# iso_sincs.net
KiCad netlist of a schematic drawn in Altium Designer
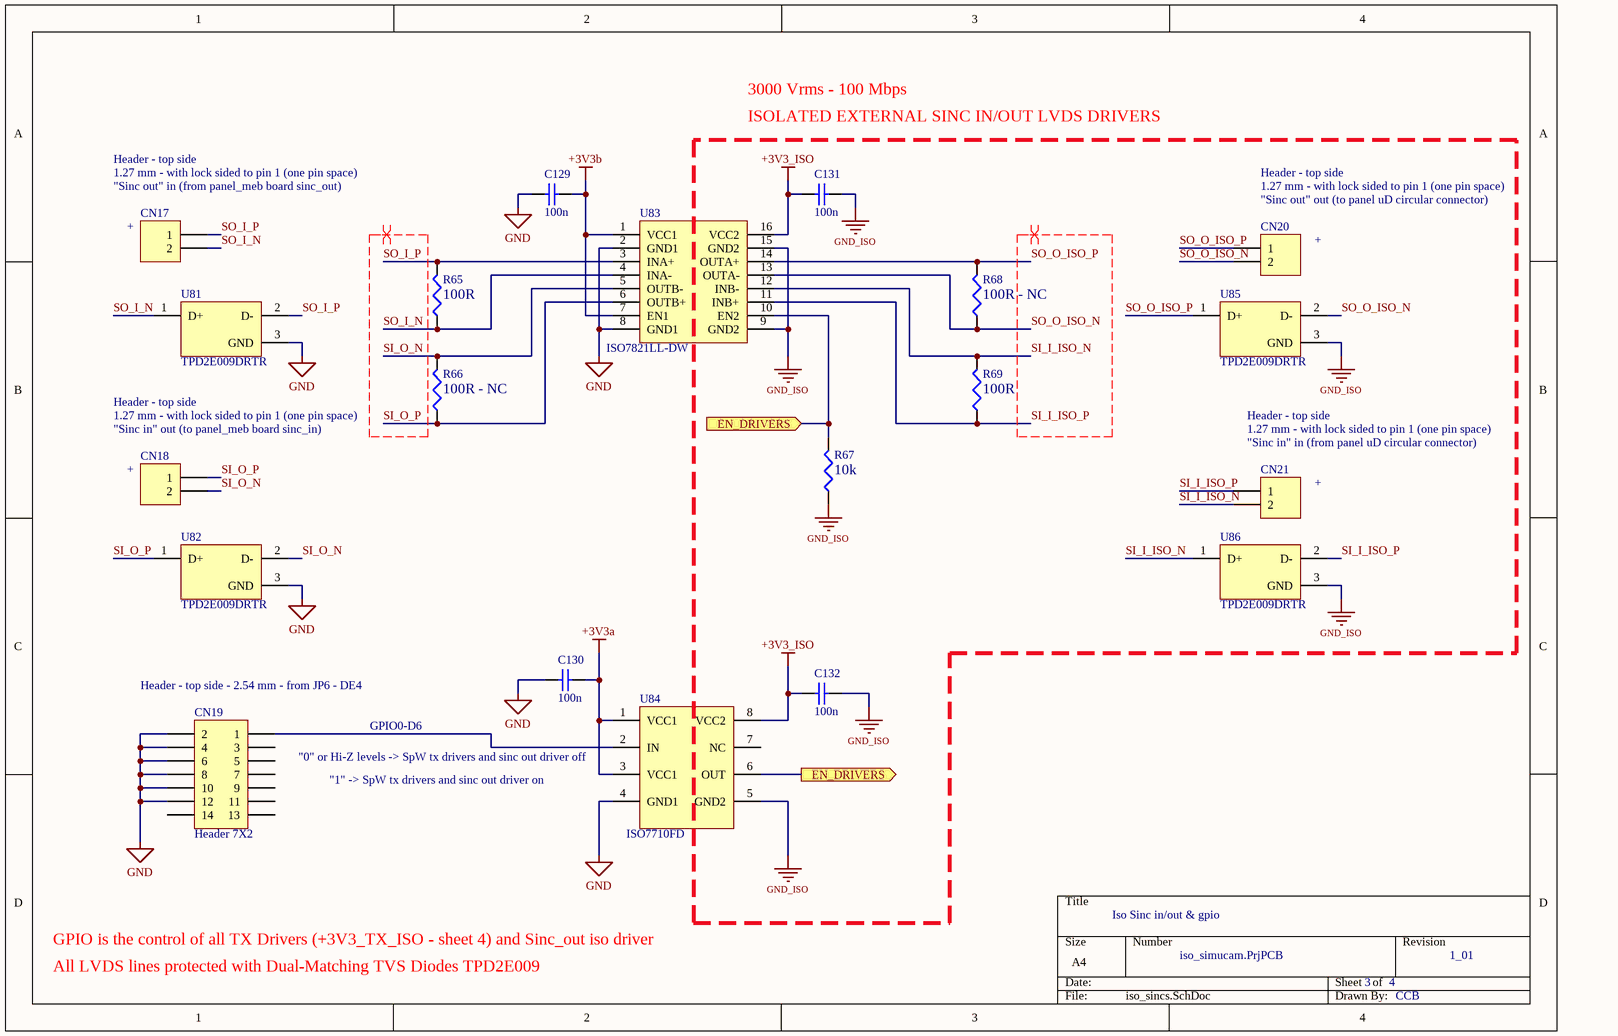
[diagram p0: iso_sincs.SchDoc]

(export (version "E")
  (design (tool "Eeschema 10.0.6"))
  (components
    (comp (ref "C129")
      (value "Capacitor Cerâmico SMD")
      (footprint "0402-cap")
      (fields (field (name "VALOR") "100n"))
      (libsource (lib "Miscellaneous Devices") (part "Capacitor Cerâmico SMD"))
    )
    (comp (ref "C130")
      (value "Capacitor Cerâmico SMD")
      (footprint "0402-cap")
      (fields (field (name "VALOR") "100n"))
      (libsource (lib "Miscellaneous Devices") (part "Capacitor Cerâmico SMD"))
    )
    (comp (ref "C131")
      (value "Capacitor Cerâmico SMD")
      (footprint "0402-cap")
      (fields (field (name "VALOR") "100n"))
      (libsource (lib "Miscellaneous Devices") (part "Capacitor Cerâmico SMD"))
    )
    (comp (ref "C132")
      (value "Capacitor Cerâmico SMD")
      (footprint "0402-cap")
      (fields (field (name "VALOR") "100n"))
      (libsource (lib "Miscellaneous Devices") (part "Capacitor Cerâmico SMD"))
    )
    (comp (ref "CN17")
      (value "MHDR1X2")
      (footprint "MHDR1X2_AXONN")
      (description "Header, 2-Pin")
      (fields (field (name "PUBLISHER") "Altium Limited"))
      (libsource (lib "") (part "MHDR1X2_1"))
    )
    (comp (ref "CN18")
      (value "MHDR1X2")
      (footprint "MHDR1X2_AXONN")
      (description "Header, 2-Pin")
      (fields (field (name "PUBLISHER") "Altium Limited"))
      (libsource (lib "") (part "MHDR1X2_1"))
    )
    (comp (ref "CN19")
      (value "Header 7X2")
      (footprint "HDR2X7")
      (description "Header, 7-Pin, Dual row")
      (fields (field (name "PUBLISHER") "Altium Limited"))
      (libsource (lib "Miscellaneous Connectors") (part "Header 7X2"))
    )
    (comp (ref "CN20")
      (value "MHDR1X2")
      (footprint "MHDR1X2_AXONN")
      (description "Header, 2-Pin")
      (fields (field (name "PUBLISHER") "Altium Limited"))
      (libsource (lib "Miscellaneous Connectors") (part "MHDR1X2"))
    )
    (comp (ref "CN21")
      (value "MHDR1X2")
      (footprint "MHDR1X2_AXONN")
      (description "Header, 2-Pin")
      (fields (field (name "PUBLISHER") "Altium Limited"))
      (libsource (lib "Miscellaneous Connectors") (part "MHDR1X2"))
    )
    (comp (ref "R65")
      (value "Res3")
      (footprint "0402-res")
      (description "Resistor")
      (fields (field (name "VALOR") "100R"))
      (libsource (lib "Miscellaneous Devices") (part "Res3"))
    )
    (comp (ref "R66")
      (value "Res3")
      (footprint "0402-res")
      (description "Resistor")
      (fields (field (name "VALOR") "100R - NC"))
      (libsource (lib "Miscellaneous Devices") (part "Res3"))
    )
    (comp (ref "R67")
      (value "Res3")
      (footprint "0402-res")
      (description "Resistor")
      (fields (field (name "VALOR") "10k"))
      (libsource (lib "Miscellaneous Devices") (part "Res3"))
    )
    (comp (ref "R68")
      (value "Res3")
      (footprint "0402-res")
      (description "Resistor")
      (fields (field (name "VALOR") "100R - NC"))
      (libsource (lib "Miscellaneous Devices") (part "Res3"))
    )
    (comp (ref "R69")
      (value "Res3")
      (footprint "0402-res")
      (description "Resistor")
      (fields (field (name "VALOR") "100R"))
      (libsource (lib "Miscellaneous Devices") (part "Res3"))
    )
    (comp (ref "U81")
      (value "TPD2E009DRTR")
      (footprint "DRT3")
      (fields (field (name "MANUFACTURER") "Texas Instruments"))
      (libsource (lib "TI Interface ESD EMI Protection") (part "TPD2E009DRTR"))
    )
    (comp (ref "U82")
      (value "TPD2E009DRTR")
      (footprint "DRT3")
      (fields (field (name "MANUFACTURER") "Texas Instruments"))
      (libsource (lib "TI Interface ESD EMI Protection") (part "TPD2E009DRTR"))
    )
    (comp (ref "U83")
      (value "ISO7821LL-DW")
      (footprint "SOIC-16-DW")
      (description "High-Performance, 8000-VPK Reinforced Isolated Dual-LVDS Buffer")
      (fields (field (name "PUBLISHER") "Altium Limited"))
      (libsource (lib "ti_isolators") (part "ISO7821LL-DW"))
    )
    (comp (ref "U84")
      (value "ISO7710FD")
      (footprint "SOIC-8")
      (description "High Speed, Robust EMC Reinforced Single-Channel Digital Isolator")
      (fields (field (name "PUBLISHER") "Altium Limited"))
      (libsource (lib "ti_isolators") (part "ISO7710FD"))
    )
    (comp (ref "U85")
      (value "TPD2E009DRTR")
      (footprint "DRT3")
      (fields (field (name "MANUFACTURER") "Texas Instruments"))
      (libsource (lib "TI Interface ESD EMI Protection") (part "TPD2E009DRTR"))
    )
    (comp (ref "U86")
      (value "TPD2E009DRTR")
      (footprint "DRT3")
      (fields (field (name "MANUFACTURER") "Texas Instruments"))
      (libsource (lib "TI Interface ESD EMI Protection") (part "TPD2E009DRTR"))
    )
  )
  (nets
    (net (code "1") (name "+3V3_ISO") (class "Default")
      (node (ref "C131") (pin "1") (pinfunction "1_1") (pintype "passive"))
      (node (ref "C132") (pin "2") (pinfunction "2_2") (pintype "passive"))
      (node (ref "U83") (pin "16") (pinfunction "VCC2_16") (pintype "passive"))
      (node (ref "U84") (pin "8") (pinfunction "VCC2_8") (pintype "passive"))
    )
    (net (code "2") (name "+3V3a") (class "Default")
      (node (ref "C130") (pin "1") (pinfunction "1_1") (pintype "passive"))
      (node (ref "U84") (pin "1") (pinfunction "VCC1_1") (pintype "passive"))
      (node (ref "U84") (pin "3") (pinfunction "VCC1_3") (pintype "passive"))
    )
    (net (code "3") (name "+3V3b") (class "Default")
      (node (ref "C129") (pin "2") (pinfunction "2_2") (pintype "passive"))
      (node (ref "U83") (pin "1") (pinfunction "VCC1_1") (pintype "passive"))
      (node (ref "U83") (pin "7") (pinfunction "EN1_7") (pintype "passive"))
    )
    (net (code "4") (name "/EN_DRIVERS") (class "Default")
      (node (ref "R67") (pin "2") (pinfunction "2_2") (pintype "passive"))
      (node (ref "U83") (pin "10") (pinfunction "EN2_10") (pintype "passive"))
      (node (ref "U84") (pin "6") (pinfunction "OUT_6") (pintype "passive"))
    )
    (net (code "5") (name "/SI_I_ISO_N") (class "Default")
      (node (ref "CN21") (pin "2") (pinfunction "2_2") (pintype "passive"))
      (node (ref "R69") (pin "2") (pinfunction "2_2") (pintype "passive"))
      (node (ref "U83") (pin "12") (pinfunction "INB-_12") (pintype "passive"))
      (node (ref "U86") (pin "1") (pinfunction "D+_1") (pintype "passive"))
    )
    (net (code "6") (name "/SI_I_ISO_P") (class "Default")
      (node (ref "CN21") (pin "1") (pinfunction "1_1") (pintype "passive"))
      (node (ref "R69") (pin "1") (pinfunction "1_1") (pintype "passive"))
      (node (ref "U83") (pin "11") (pinfunction "INB+_11") (pintype "passive"))
      (node (ref "U86") (pin "2") (pinfunction "D-_2") (pintype "passive"))
    )
    (net (code "7") (name "/SI_O_N") (class "Default")
      (node (ref "CN18") (pin "2") (pinfunction "2_2") (pintype "passive"))
      (node (ref "R66") (pin "2") (pinfunction "2_2") (pintype "passive"))
      (node (ref "U82") (pin "2") (pinfunction "D-_2") (pintype "passive"))
      (node (ref "U83") (pin "5") (pinfunction "OUTB-_5") (pintype "passive"))
    )
    (net (code "8") (name "/SI_O_P") (class "Default")
      (node (ref "CN18") (pin "1") (pinfunction "1_1") (pintype "passive"))
      (node (ref "R66") (pin "1") (pinfunction "1_1") (pintype "passive"))
      (node (ref "U82") (pin "1") (pinfunction "D+_1") (pintype "passive"))
      (node (ref "U83") (pin "6") (pinfunction "OUTB+_6") (pintype "passive"))
    )
    (net (code "9") (name "/SO_I_N") (class "Default")
      (node (ref "CN17") (pin "2") (pinfunction "2_2") (pintype "passive"))
      (node (ref "R65") (pin "1") (pinfunction "1_1") (pintype "passive"))
      (node (ref "U81") (pin "1") (pinfunction "D+_1") (pintype "passive"))
      (node (ref "U83") (pin "4") (pinfunction "INA-_4") (pintype "passive"))
    )
    (net (code "10") (name "/SO_I_P") (class "Default")
      (node (ref "CN17") (pin "1") (pinfunction "1_1") (pintype "passive"))
      (node (ref "R65") (pin "2") (pinfunction "2_2") (pintype "passive"))
      (node (ref "U81") (pin "2") (pinfunction "D-_2") (pintype "passive"))
      (node (ref "U83") (pin "3") (pinfunction "INA+_3") (pintype "passive"))
    )
    (net (code "11") (name "/SO_O_ISO_N") (class "Default")
      (node (ref "CN20") (pin "2") (pinfunction "2_2") (pintype "passive"))
      (node (ref "R68") (pin "1") (pinfunction "1_1") (pintype "passive"))
      (node (ref "U83") (pin "13") (pinfunction "OUTA-_13") (pintype "passive"))
      (node (ref "U85") (pin "2") (pinfunction "D-_2") (pintype "passive"))
    )
    (net (code "12") (name "/SO_O_ISO_P") (class "Default")
      (node (ref "CN20") (pin "1") (pinfunction "1_1") (pintype "passive"))
      (node (ref "R68") (pin "2") (pinfunction "2_2") (pintype "passive"))
      (node (ref "U83") (pin "14") (pinfunction "OUTA+_14") (pintype "passive"))
      (node (ref "U85") (pin "1") (pinfunction "D+_1") (pintype "passive"))
    )
    (net (code "13") (name "GND") (class "Default")
      (node (ref "C129") (pin "1") (pinfunction "1_1") (pintype "passive"))
      (node (ref "C130") (pin "2") (pinfunction "2_2") (pintype "passive"))
      (node (ref "CN19") (pin "10") (pinfunction "10_10") (pintype "passive"))
      (node (ref "CN19") (pin "12") (pinfunction "12_12") (pintype "passive"))
      (node (ref "CN19") (pin "2") (pinfunction "2_2") (pintype "passive"))
      (node (ref "CN19") (pin "4") (pinfunction "4_4") (pintype "passive"))
      (node (ref "CN19") (pin "6") (pinfunction "6_6") (pintype "passive"))
      (node (ref "CN19") (pin "8") (pinfunction "8_8") (pintype "passive"))
      (node (ref "U81") (pin "3") (pinfunction "GND_3") (pintype "power_in"))
      (node (ref "U82") (pin "3") (pinfunction "GND_3") (pintype "power_in"))
      (node (ref "U83") (pin "2") (pinfunction "GND1_2") (pintype "passive"))
      (node (ref "U83") (pin "8") (pinfunction "GND1_8") (pintype "passive"))
      (node (ref "U84") (pin "4") (pinfunction "GND1_4") (pintype "passive"))
    )
    (net (code "14") (name "GND_ISO") (class "Default")
      (node (ref "C131") (pin "2") (pinfunction "2_2") (pintype "passive"))
      (node (ref "C132") (pin "1") (pinfunction "1_1") (pintype "passive"))
      (node (ref "R67") (pin "1") (pinfunction "1_1") (pintype "passive"))
      (node (ref "U83") (pin "15") (pinfunction "GND2_15") (pintype "passive"))
      (node (ref "U83") (pin "9") (pinfunction "GND2_9") (pintype "passive"))
      (node (ref "U84") (pin "5") (pinfunction "GND2_5") (pintype "passive"))
      (node (ref "U85") (pin "3") (pinfunction "GND_3") (pintype "power_in"))
      (node (ref "U86") (pin "3") (pinfunction "GND_3") (pintype "power_in"))
    )
    (net (code "15") (name "Net-(U84-IN)") (class "Default")
      (node (ref "CN19") (pin "1") (pinfunction "1_1") (pintype "passive"))
      (node (ref "U84") (pin "2") (pinfunction "IN_2") (pintype "passive"))
    )
    (net (code "16") (name "unconnected-(CN19-Pad3)") (class "Default")
      (node (ref "CN19") (pin "3") (pinfunction "3_3") (pintype "passive"))
    )
    (net (code "17") (name "unconnected-(CN19-Pad5)") (class "Default")
      (node (ref "CN19") (pin "5") (pinfunction "5_5") (pintype "passive"))
    )
    (net (code "18") (name "unconnected-(CN19-Pad7)") (class "Default")
      (node (ref "CN19") (pin "7") (pinfunction "7_7") (pintype "passive"))
    )
    (net (code "19") (name "unconnected-(CN19-Pad9)") (class "Default")
      (node (ref "CN19") (pin "9") (pinfunction "9_9") (pintype "passive"))
    )
    (net (code "20") (name "unconnected-(CN19-Pad11)") (class "Default")
      (node (ref "CN19") (pin "11") (pinfunction "11_11") (pintype "passive"))
    )
    (net (code "21") (name "unconnected-(CN19-Pad13)") (class "Default")
      (node (ref "CN19") (pin "13") (pinfunction "13_13") (pintype "passive"))
    )
    (net (code "22") (name "unconnected-(CN19-Pad14)") (class "Default")
      (node (ref "CN19") (pin "14") (pinfunction "14_14") (pintype "passive"))
    )
    (net (code "23") (name "unconnected-(U84-NC-Pad7)") (class "Default")
      (node (ref "U84") (pin "7") (pinfunction "NC_7") (pintype "passive"))
    )
  )
)
